# SCH_weirdoproject_2024-06-13.net
KiCad netlist of a schematic drawn in EasyEDA
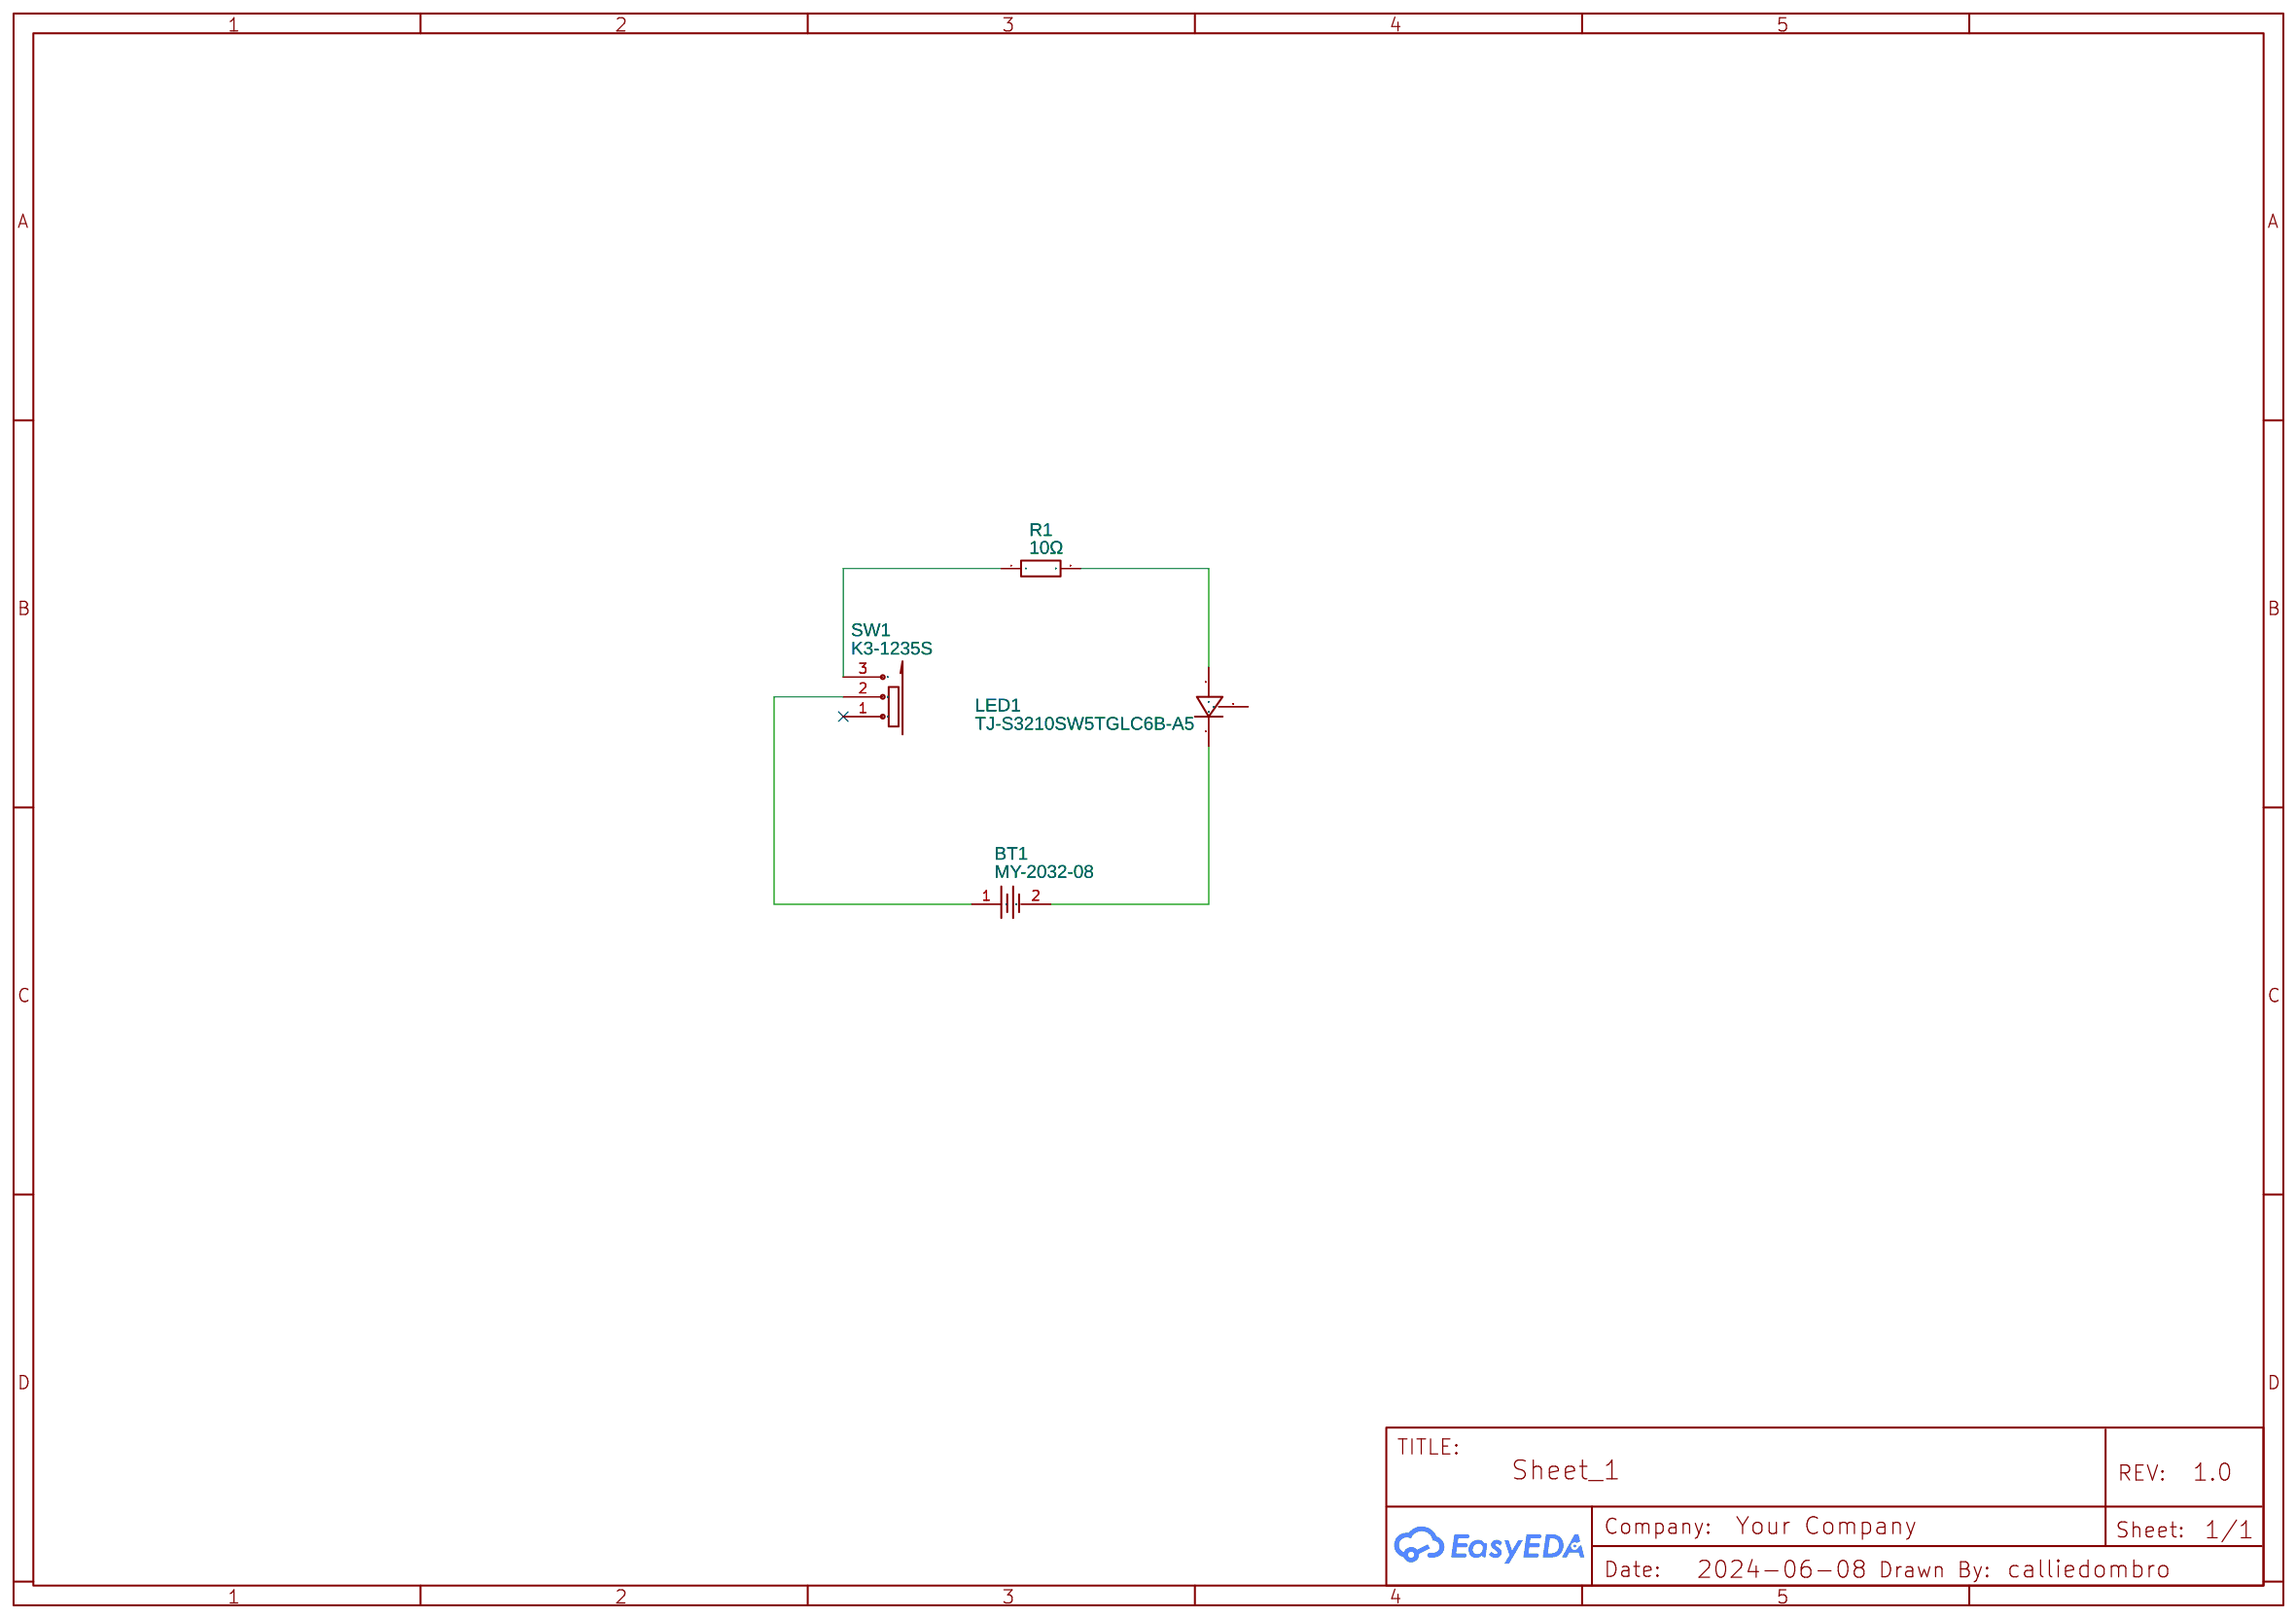
[diagram p0: schematic sheet]

(export (version "E")
  (design (tool "Eeschema 10.0.6"))
  (components
    (comp (ref "BT1")
      (value "MY-2032-08")
      (fields (field (name "Manufacturer") "MYOUNG(美阳)"))
      (libsource (lib "") (part "MY-2032-08"))
    )
    (comp (ref "LED1")
      (value "TJ-S3210SW5TGLC6B-A5")
      (fields (field (name "Manufacturer") "TOGIALED(统佳)"))
      (libsource (lib "") (part "TJ-S3210SW5TGLC6B-A5"))
    )
    (comp (ref "R1")
      (value "10Ω")
      (fields
        (field (name "Manufacturer Part") "0603WAF100JT5E")
        (field (name "Manufacturer") "UNI-ROYAL(厚声)")
      )
      (libsource (lib "") (part "0603WAF100JT5E"))
    )
    (comp (ref "SW1")
      (value "K3-1235S")
      (fields (field (name "Manufacturer Part") "K3-1235S-F1") (field (name "Manufacturer") "韩国韩荣"))
      (libsource (lib "") (part "K3-1235S"))
    )
  )
  (nets
    (net (code "1") (name "Net-(BT1-Pad1)") (class "Default")
      (node (ref "BT1") (pin "1") (pinfunction "1_1") (pintype "input"))
      (node (ref "SW1") (pin "2") (pinfunction "2_2") (pintype "unspecified"))
    )
    (net (code "2") (name "Net-(BT1-Pad2)") (class "Default")
      (node (ref "BT1") (pin "2") (pinfunction "2_2") (pintype "input"))
      (node (ref "LED1") (pin "1") (pinfunction "1_1") (pintype "unspecified"))
    )
    (net (code "3") (name "Net-(LED1-Pad2)") (class "Default")
      (node (ref "LED1") (pin "2") (pinfunction "2_2") (pintype "unspecified"))
      (node (ref "R1") (pin "2") (pinfunction "2_2") (pintype "input"))
    )
    (net (code "4") (name "Net-(R1-Pad1)") (class "Default")
      (node (ref "R1") (pin "1") (pinfunction "1_1") (pintype "input"))
      (node (ref "SW1") (pin "3") (pinfunction "3_3") (pintype "unspecified"))
    )
    (net (code "5") (name "unconnected-(LED1-Pad3)") (class "Default")
      (node (ref "LED1") (pin "3") (pinfunction "3_3") (pintype "unspecified"))
    )
    (net (code "6") (name "unconnected-(SW1-Pad1)") (class "Default")
      (node (ref "SW1") (pin "1") (pinfunction "1_1") (pintype "unspecified+no_connect"))
    )
  )
)
